# untitled.net
KiCad netlist of a schematic drawn in EAGLE
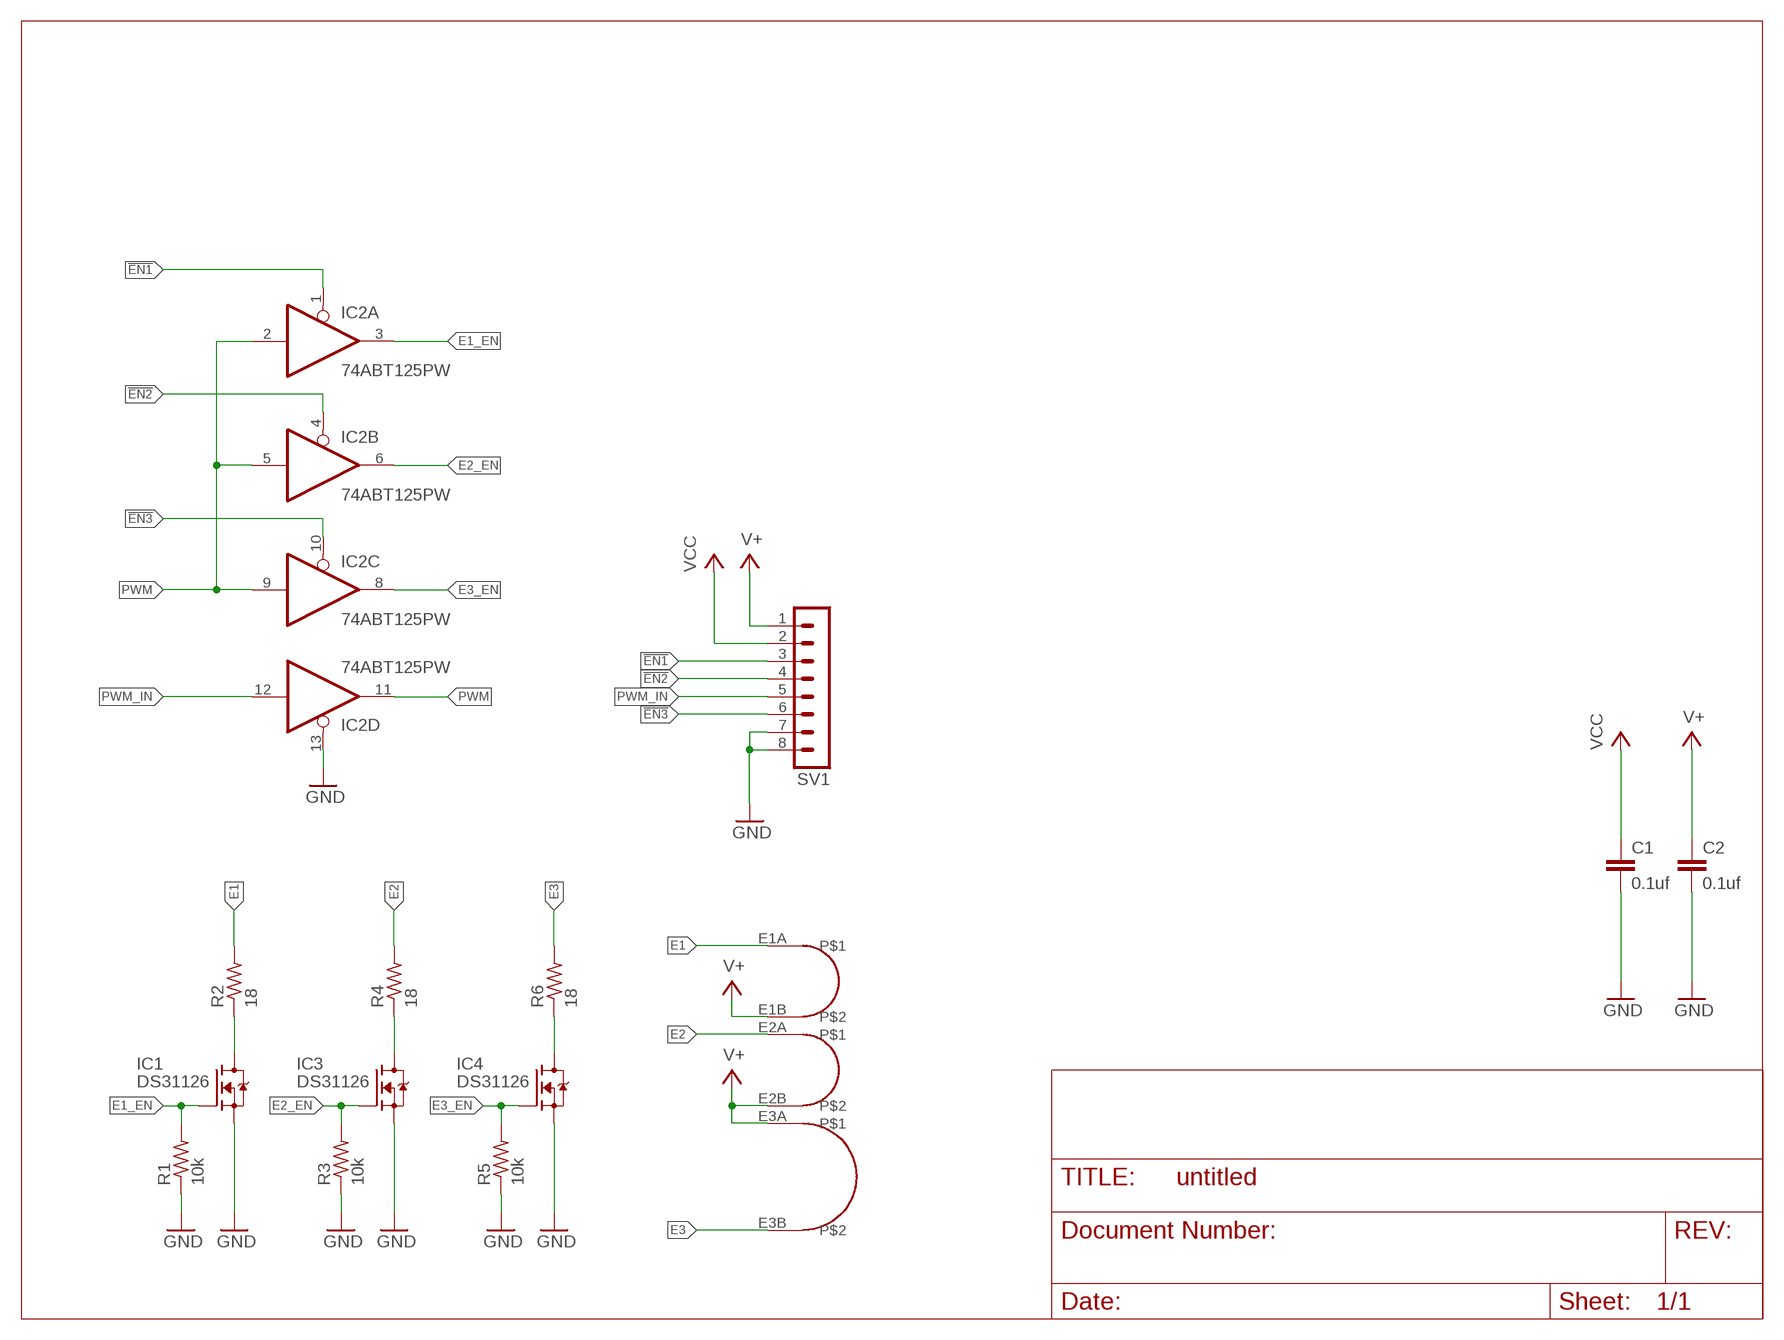
[diagram p0: schematic, sheet 1]

(export (version "E")
  (design (tool "Eeschema 10.0.6"))
  (components
    (comp (ref "C1")
      (value "0.1uf")
      (footprint "eagle-import:C0603")
      (libsource (lib "eagle-import") (part "C-EUC0603"))
    )
    (comp (ref "C2")
      (value "0.1uf")
      (footprint "eagle-import:C0603")
      (libsource (lib "eagle-import") (part "C-EUC0603"))
    )
    (comp (ref "IC1")
      (value "DS31126")
      (footprint "eagle-import:SOT23")
      (libsource (lib "eagle-import") (part "DS31126"))
    )
    (comp (ref "IC2")
      (value "74ABT125PW")
      (footprint "eagle-import:TSSOP14")
      (libsource (lib "eagle-import") (part "74125PWABT"))
    )
    (comp (ref "IC3")
      (value "DS31126")
      (footprint "eagle-import:SOT23")
      (libsource (lib "eagle-import") (part "DS31126"))
    )
    (comp (ref "IC4")
      (value "DS31126")
      (footprint "eagle-import:SOT23")
      (libsource (lib "eagle-import") (part "DS31126"))
    )
    (comp (ref "NICR1")
      (value "HOT_WIRE")
      (footprint "eagle-import:LAYOUT_A")
      (libsource (lib "eagle-import") (part "HOT_WIRE"))
    )
    (comp (ref "R1")
      (value "10k")
      (footprint "eagle-import:R0603")
      (libsource (lib "eagle-import") (part "R-US_R0603"))
    )
    (comp (ref "R2")
      (value "18")
      (footprint "eagle-import:R2512W")
      (libsource (lib "eagle-import") (part "R-US_R2512W"))
    )
    (comp (ref "R3")
      (value "10k")
      (footprint "eagle-import:R0603")
      (libsource (lib "eagle-import") (part "R-US_R0603"))
    )
    (comp (ref "R4")
      (value "18")
      (footprint "eagle-import:R2512W")
      (libsource (lib "eagle-import") (part "R-US_R2512W"))
    )
    (comp (ref "R5")
      (value "10k")
      (footprint "eagle-import:R0603")
      (libsource (lib "eagle-import") (part "R-US_R0603"))
    )
    (comp (ref "R6")
      (value "18")
      (footprint "eagle-import:R2512W")
      (libsource (lib "eagle-import") (part "R-US_R2512W"))
    )
    (comp (ref "SV1")
      (value "MA08-1")
      (footprint "eagle-import:MA08-1")
      (libsource (lib "eagle-import") (part "MA08-1"))
    )
  )
  (nets
    (net (code "1") (name "/~{EN1}") (class "Default")
      (node (ref "IC2") (pin "1") (pinfunction "OE_1") (pintype "input"))
      (node (ref "SV1") (pin "3") (pinfunction "3_3") (pintype "passive"))
    )
    (net (code "2") (name "/~{EN2}") (class "Default")
      (node (ref "IC2") (pin "4") (pinfunction "OE_4") (pintype "input"))
      (node (ref "SV1") (pin "4") (pinfunction "4_4") (pintype "passive"))
    )
    (net (code "3") (name "/~{EN3}") (class "Default")
      (node (ref "IC2") (pin "10") (pinfunction "OE_10") (pintype "input"))
      (node (ref "SV1") (pin "6") (pinfunction "6_6") (pintype "passive"))
    )
    (net (code "4") (name "E1") (class "Default")
      (node (ref "NICR1") (pin "E1A") (pinfunction "P$1_E1A") (pintype "bidirectional"))
      (node (ref "R2") (pin "2") (pinfunction "2_2") (pintype "passive"))
    )
    (net (code "5") (name "E1_EN") (class "Default")
      (node (ref "IC1") (pin "G") (pinfunction "G_G") (pintype "passive"))
      (node (ref "IC2") (pin "3") (pinfunction "O_3") (pintype "tri_state"))
      (node (ref "R1") (pin "2") (pinfunction "2_2") (pintype "passive"))
    )
    (net (code "6") (name "E2") (class "Default")
      (node (ref "NICR1") (pin "E2A") (pinfunction "P$1_E2A") (pintype "bidirectional"))
      (node (ref "R4") (pin "2") (pinfunction "2_2") (pintype "passive"))
    )
    (net (code "7") (name "E2_EN") (class "Default")
      (node (ref "IC2") (pin "6") (pinfunction "O_6") (pintype "tri_state"))
      (node (ref "IC3") (pin "G") (pinfunction "G_G") (pintype "passive"))
      (node (ref "R3") (pin "2") (pinfunction "2_2") (pintype "passive"))
    )
    (net (code "8") (name "E3") (class "Default")
      (node (ref "NICR1") (pin "E3B") (pinfunction "P$2_E3B") (pintype "bidirectional"))
      (node (ref "R6") (pin "2") (pinfunction "2_2") (pintype "passive"))
    )
    (net (code "9") (name "E3_EN") (class "Default")
      (node (ref "IC2") (pin "8") (pinfunction "O_8") (pintype "tri_state"))
      (node (ref "IC4") (pin "G") (pinfunction "G_G") (pintype "passive"))
      (node (ref "R5") (pin "2") (pinfunction "2_2") (pintype "passive"))
    )
    (net (code "10") (name "GND") (class "Default")
      (node (ref "C1") (pin "2") (pinfunction "2_2") (pintype "passive"))
      (node (ref "C2") (pin "2") (pinfunction "2_2") (pintype "passive"))
      (node (ref "IC1") (pin "S") (pinfunction "S_S") (pintype "passive"))
      (node (ref "IC2") (pin "13") (pinfunction "OE_13") (pintype "input"))
      (node (ref "IC3") (pin "S") (pinfunction "S_S") (pintype "passive"))
      (node (ref "IC4") (pin "S") (pinfunction "S_S") (pintype "passive"))
      (node (ref "R1") (pin "1") (pinfunction "1_1") (pintype "passive"))
      (node (ref "R3") (pin "1") (pinfunction "1_1") (pintype "passive"))
      (node (ref "R5") (pin "1") (pinfunction "1_1") (pintype "passive"))
      (node (ref "SV1") (pin "7") (pinfunction "7_7") (pintype "passive"))
      (node (ref "SV1") (pin "8") (pinfunction "8_8") (pintype "passive"))
    )
    (net (code "11") (name "Net-(IC1-PadD)") (class "Default")
      (node (ref "IC1") (pin "D") (pinfunction "D_D") (pintype "passive"))
      (node (ref "R2") (pin "1") (pinfunction "1_1") (pintype "passive"))
    )
    (net (code "12") (name "Net-(IC3-PadD)") (class "Default")
      (node (ref "IC3") (pin "D") (pinfunction "D_D") (pintype "passive"))
      (node (ref "R4") (pin "1") (pinfunction "1_1") (pintype "passive"))
    )
    (net (code "13") (name "Net-(IC4-PadD)") (class "Default")
      (node (ref "IC4") (pin "D") (pinfunction "D_D") (pintype "passive"))
      (node (ref "R6") (pin "1") (pinfunction "1_1") (pintype "passive"))
    )
    (net (code "14") (name "PWM") (class "Default")
      (node (ref "IC2") (pin "11") (pinfunction "O_11") (pintype "tri_state"))
      (node (ref "IC2") (pin "2") (pinfunction "I_2") (pintype "input"))
      (node (ref "IC2") (pin "5") (pinfunction "I_5") (pintype "input"))
      (node (ref "IC2") (pin "9") (pinfunction "I_9") (pintype "input"))
    )
    (net (code "15") (name "PWM_IN") (class "Default")
      (node (ref "IC2") (pin "12") (pinfunction "I_12") (pintype "input"))
      (node (ref "SV1") (pin "5") (pinfunction "5_5") (pintype "passive"))
    )
    (net (code "16") (name "V+") (class "Default")
      (node (ref "C2") (pin "1") (pinfunction "1_1") (pintype "passive"))
      (node (ref "NICR1") (pin "E1B") (pinfunction "P$2_E1B") (pintype "bidirectional"))
      (node (ref "NICR1") (pin "E2B") (pinfunction "P$2_E2B") (pintype "bidirectional"))
      (node (ref "NICR1") (pin "E3A") (pinfunction "P$1_E3A") (pintype "bidirectional"))
      (node (ref "SV1") (pin "1") (pinfunction "1_1") (pintype "passive"))
    )
    (net (code "17") (name "VCC") (class "Default")
      (node (ref "C1") (pin "1") (pinfunction "1_1") (pintype "passive"))
      (node (ref "SV1") (pin "2") (pinfunction "2_2") (pintype "passive"))
    )
  )
)
